# USB_Load.net
KiCad netlist of a schematic drawn in EAGLE
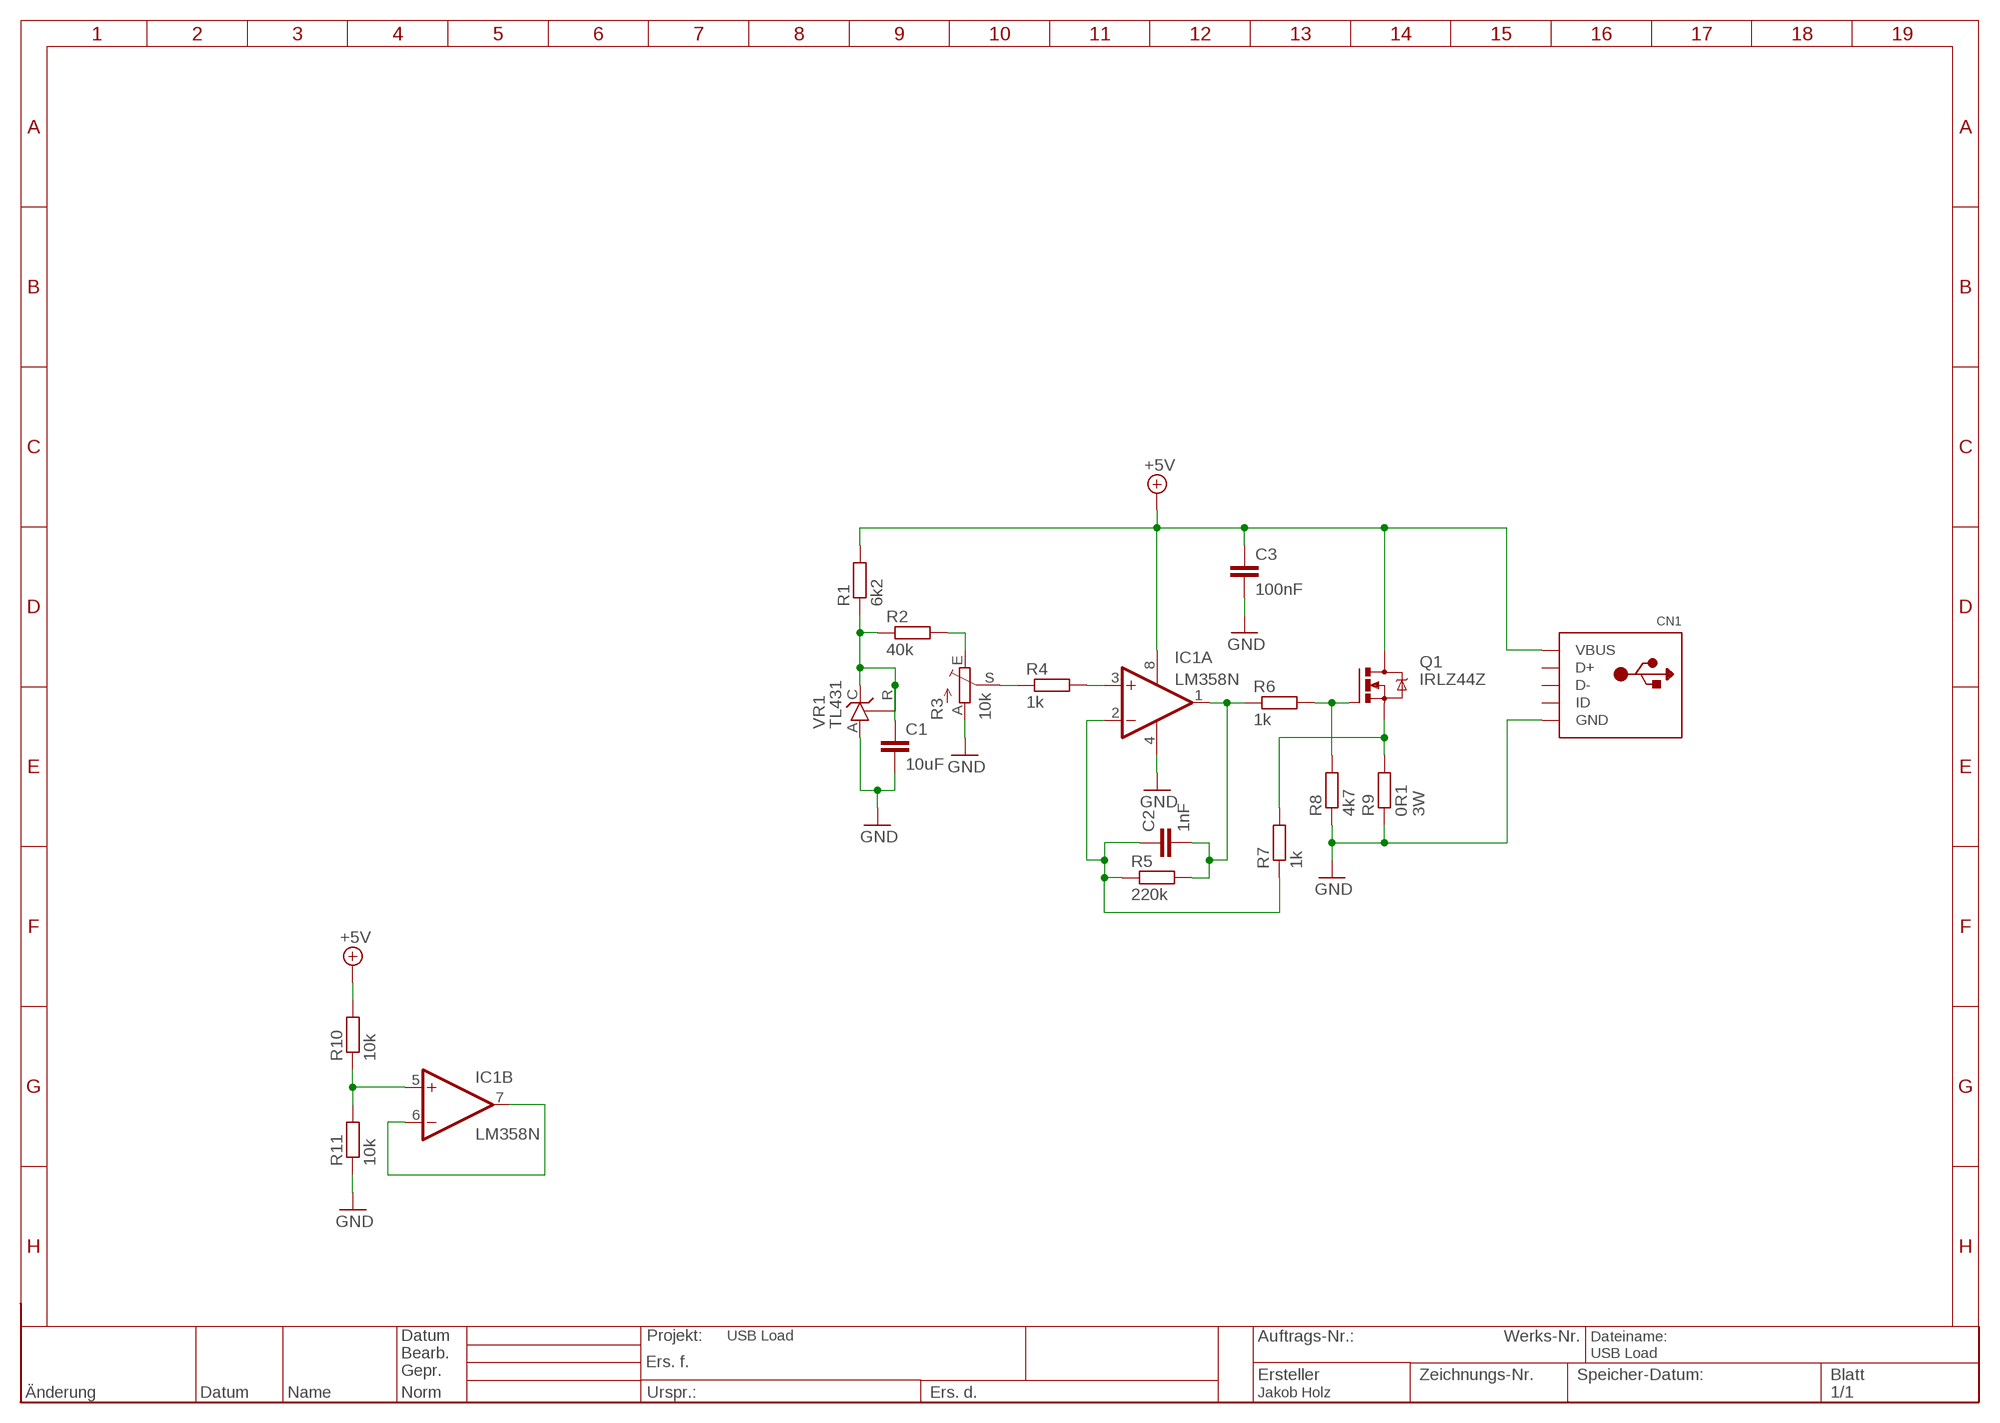
[diagram p0: schematic, sheet 1]

(export (version "E")
  (design (tool "Eeschema 10.0.6"))
  (components
    (comp (ref "C1")
      (value "10uF")
      (footprint "eagle-import:C1206")
      (libsource (lib "eagle-import") (part "C-EUC1206"))
    )
    (comp (ref "C2")
      (value "1nF")
      (footprint "eagle-import:C1206")
      (libsource (lib "eagle-import") (part "C-EUC1206"))
    )
    (comp (ref "C3")
      (value "100nF")
      (footprint "eagle-import:C1206")
      (libsource (lib "eagle-import") (part "C-EUC1206"))
    )
    (comp (ref "CN1")
      (value "USBTHM")
      (footprint "eagle-import:USB-MINIB-THM")
      (libsource (lib "eagle-import") (part "USBTHM"))
    )
    (comp (ref "IC1")
      (value "LM358N")
      (footprint "eagle-import:DIL08")
      (libsource (lib "eagle-import") (part "LM358N"))
    )
    (comp (ref "Q1")
      (value "IRLZ44Z")
      (footprint "eagle-import:TO220BH")
      (libsource (lib "eagle-import") (part "IRLZ44Z"))
    )
    (comp (ref "R1")
      (value "6k2")
      (footprint "eagle-import:R1206")
      (libsource (lib "eagle-import") (part "R-EU_R1206"))
    )
    (comp (ref "R2")
      (value "40k")
      (footprint "eagle-import:R1206")
      (libsource (lib "eagle-import") (part "R-EU_R1206"))
    )
    (comp (ref "R3")
      (value "10k")
      (footprint "eagle-import:RJ9W")
      (libsource (lib "eagle-import") (part "TRIM_EU-RJ9W"))
    )
    (comp (ref "R4")
      (value "1k")
      (footprint "eagle-import:R1206")
      (libsource (lib "eagle-import") (part "R-EU_R1206"))
    )
    (comp (ref "R5")
      (value "220k")
      (footprint "eagle-import:R1206")
      (libsource (lib "eagle-import") (part "R-EU_R1206"))
    )
    (comp (ref "R6")
      (value "1k")
      (footprint "eagle-import:R1206")
      (libsource (lib "eagle-import") (part "R-EU_R1206"))
    )
    (comp (ref "R7")
      (value "1k")
      (footprint "eagle-import:R1206")
      (libsource (lib "eagle-import") (part "R-EU_R1206"))
    )
    (comp (ref "R8")
      (value "4k7")
      (footprint "eagle-import:R1206")
      (libsource (lib "eagle-import") (part "R-EU_R1206"))
    )
    (comp (ref "R9")
      (value "0R1")
      (footprint "eagle-import:R1206")
      (libsource (lib "eagle-import") (part "R-EU_R1206"))
    )
    (comp (ref "R10")
      (value "10k")
      (footprint "eagle-import:R1206")
      (libsource (lib "eagle-import") (part "R-EU_R1206"))
    )
    (comp (ref "R11")
      (value "10k")
      (footprint "eagle-import:R1206")
      (libsource (lib "eagle-import") (part "R-EU_R1206"))
    )
    (comp (ref "VR1")
      (value "TL431")
      (footprint "eagle-import:TO92-CLP")
      (libsource (lib "eagle-import") (part "TL431CLP"))
    )
  )
  (nets
    (net (code "1") (name "+5V") (class "Default")
      (node (ref "C3") (pin "1") (pinfunction "1_1") (pintype "passive"))
      (node (ref "CN1") (pin "VBUS") (pinfunction "VBUS_VBUS") (pintype "power_in"))
      (node (ref "IC1") (pin "8") (pinfunction "V+_8") (pintype "power_in"))
      (node (ref "Q1") (pin "D") (pinfunction "D_D") (pintype "passive"))
      (node (ref "R1") (pin "2") (pinfunction "2_2") (pintype "passive"))
      (node (ref "R10") (pin "2") (pinfunction "2_2") (pintype "passive"))
    )
    (net (code "2") (name "GND") (class "Default")
      (node (ref "C1") (pin "2") (pinfunction "2_2") (pintype "passive"))
      (node (ref "C3") (pin "2") (pinfunction "2_2") (pintype "passive"))
      (node (ref "CN1") (pin "GND") (pinfunction "GND_GND") (pintype "power_in"))
      (node (ref "IC1") (pin "4") (pinfunction "V-_4") (pintype "power_in"))
      (node (ref "R11") (pin "1") (pinfunction "1_1") (pintype "passive"))
      (node (ref "R3") (pin "A") (pinfunction "A_A") (pintype "passive"))
      (node (ref "R8") (pin "1") (pinfunction "1_1") (pintype "passive"))
      (node (ref "R9") (pin "1") (pinfunction "1_1") (pintype "passive"))
      (node (ref "VR1") (pin "A") (pinfunction "A_A") (pintype "passive"))
    )
    (net (code "3") (name "Net-(C1-Pad1)") (class "Default")
      (node (ref "C1") (pin "1") (pinfunction "1_1") (pintype "passive"))
      (node (ref "R1") (pin "1") (pinfunction "1_1") (pintype "passive"))
      (node (ref "R2") (pin "1") (pinfunction "1_1") (pintype "passive"))
      (node (ref "VR1") (pin "C") (pinfunction "C_C") (pintype "passive"))
      (node (ref "VR1") (pin "R") (pinfunction "R_R") (pintype "passive"))
    )
    (net (code "4") (name "Net-(IC1A-+IN)") (class "Default")
      (node (ref "IC1") (pin "3") (pinfunction "+IN_3") (pintype "input"))
      (node (ref "R4") (pin "2") (pinfunction "2_2") (pintype "passive"))
    )
    (net (code "5") (name "Net-(IC1A--IN)") (class "Default")
      (node (ref "C2") (pin "1") (pinfunction "1_1") (pintype "passive"))
      (node (ref "IC1") (pin "2") (pinfunction "-IN_2") (pintype "input"))
      (node (ref "R5") (pin "1") (pinfunction "1_1") (pintype "passive"))
      (node (ref "R7") (pin "1") (pinfunction "1_1") (pintype "passive"))
    )
    (net (code "6") (name "Net-(IC1A-OUT)") (class "Default")
      (node (ref "C2") (pin "2") (pinfunction "2_2") (pintype "passive"))
      (node (ref "IC1") (pin "1") (pinfunction "OUT_1") (pintype "output"))
      (node (ref "R5") (pin "2") (pinfunction "2_2") (pintype "passive"))
      (node (ref "R6") (pin "1") (pinfunction "1_1") (pintype "passive"))
    )
    (net (code "7") (name "Net-(IC1B-+IN)") (class "Default")
      (node (ref "IC1") (pin "5") (pinfunction "+IN_5") (pintype "input"))
      (node (ref "R10") (pin "1") (pinfunction "1_1") (pintype "passive"))
      (node (ref "R11") (pin "2") (pinfunction "2_2") (pintype "passive"))
    )
    (net (code "8") (name "Net-(IC1B--IN)") (class "Default")
      (node (ref "IC1") (pin "6") (pinfunction "-IN_6") (pintype "input"))
      (node (ref "IC1") (pin "7") (pinfunction "OUT_7") (pintype "output"))
    )
    (net (code "9") (name "Net-(Q1-PadG)") (class "Default")
      (node (ref "Q1") (pin "G") (pinfunction "G_G") (pintype "passive"))
      (node (ref "R6") (pin "2") (pinfunction "2_2") (pintype "passive"))
      (node (ref "R8") (pin "2") (pinfunction "2_2") (pintype "passive"))
    )
    (net (code "10") (name "Net-(Q1-PadS)") (class "Default")
      (node (ref "Q1") (pin "S") (pinfunction "S_S") (pintype "passive"))
      (node (ref "R7") (pin "2") (pinfunction "2_2") (pintype "passive"))
      (node (ref "R9") (pin "2") (pinfunction "2_2") (pintype "passive"))
    )
    (net (code "11") (name "Net-(R2-Pad2)") (class "Default")
      (node (ref "R2") (pin "2") (pinfunction "2_2") (pintype "passive"))
      (node (ref "R3") (pin "E") (pinfunction "E_E") (pintype "passive"))
    )
    (net (code "12") (name "Net-(R3-PadS)") (class "Default")
      (node (ref "R3") (pin "S") (pinfunction "S_S") (pintype "passive"))
      (node (ref "R4") (pin "1") (pinfunction "1_1") (pintype "passive"))
    )
    (net (code "13") (name "unconnected-(CN1-PadD+)") (class "Default")
      (node (ref "CN1") (pin "D+") (pinfunction "D+_D+") (pintype "bidirectional"))
    )
    (net (code "14") (name "unconnected-(CN1-PadD-)") (class "Default")
      (node (ref "CN1") (pin "D-") (pinfunction "D-_D-") (pintype "bidirectional"))
    )
    (net (code "15") (name "unconnected-(CN1-PadID)") (class "Default")
      (node (ref "CN1") (pin "ID") (pinfunction "ID_ID") (pintype "bidirectional"))
    )
  )
)
